# eVV_TopLevel_TMC.net
KiCad netlist of a schematic drawn in Altium Designer
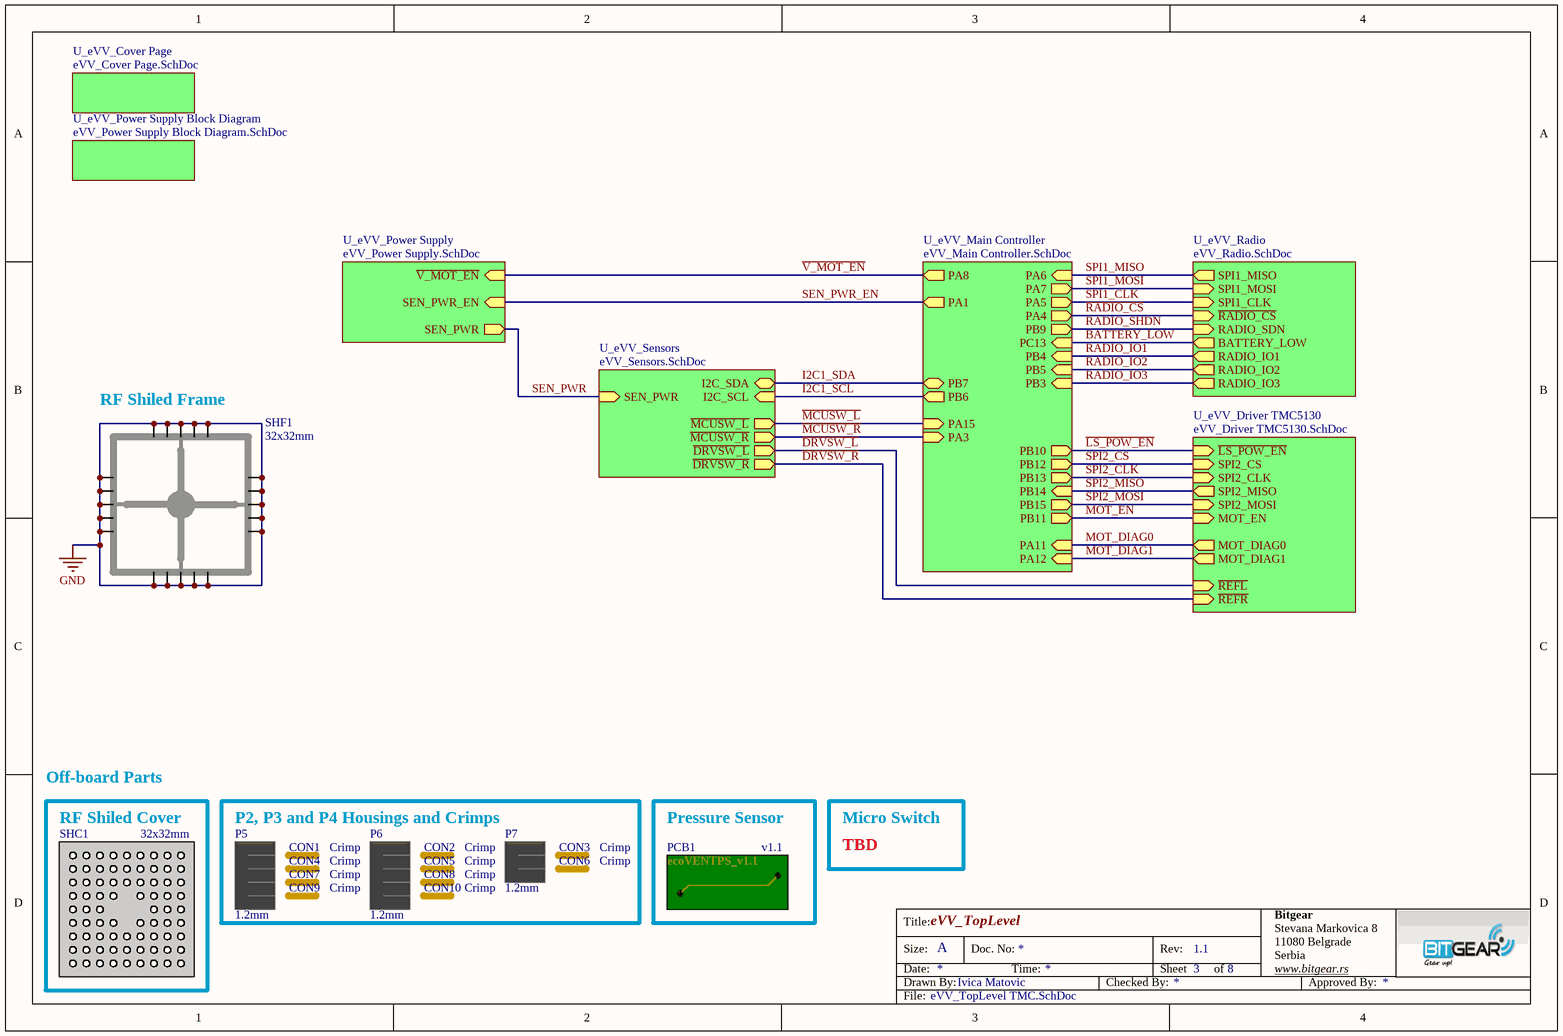
[diagram p0: eVV_TopLevel TMC.SchDoc]

(export (version "E")
  (design (tool "Eeschema 10.0.6"))
  (components
    (comp (ref "CON1")
      (value "Crimp")
      (description "Molex Contact for Pico-EZmate")
      (fields (field (name "MANUFACTURER") "Molex"))
      (libsource (lib "ecoVENTV") (part "0781720410"))
    )
    (comp (ref "CON2")
      (value "Crimp")
      (description "Molex Contact for Pico-EZmate")
      (fields (field (name "MANUFACTURER") "Molex"))
      (libsource (lib "ecoVENTV") (part "0781720410"))
    )
    (comp (ref "CON3")
      (value "Crimp")
      (description "Molex Contact for Pico-EZmate")
      (fields (field (name "MANUFACTURER") "Molex"))
      (libsource (lib "ecoVENTV") (part "0781720410"))
    )
    (comp (ref "CON4")
      (value "Crimp")
      (description "Molex Contact for Pico-EZmate")
      (fields (field (name "MANUFACTURER") "Molex"))
      (libsource (lib "ecoVENTV") (part "0781720410"))
    )
    (comp (ref "CON5")
      (value "Crimp")
      (description "Molex Contact for Pico-EZmate")
      (fields (field (name "MANUFACTURER") "Molex"))
      (libsource (lib "ecoVENTV") (part "0781720410"))
    )
    (comp (ref "CON6")
      (value "Crimp")
      (description "Molex Contact for Pico-EZmate")
      (fields (field (name "MANUFACTURER") "Molex"))
      (libsource (lib "ecoVENTV") (part "0781720410"))
    )
    (comp (ref "CON7")
      (value "Crimp")
      (description "Molex Contact for Pico-EZmate")
      (fields (field (name "MANUFACTURER") "Molex"))
      (libsource (lib "ecoVENTV") (part "0781720410"))
    )
    (comp (ref "CON8")
      (value "Crimp")
      (description "Molex Contact for Pico-EZmate")
      (fields (field (name "MANUFACTURER") "Molex"))
      (libsource (lib "ecoVENTV") (part "0781720410"))
    )
    (comp (ref "CON9")
      (value "Crimp")
      (description "Molex Contact for Pico-EZmate")
      (fields (field (name "MANUFACTURER") "Molex"))
      (libsource (lib "ecoVENTV") (part "0781720410"))
    )
    (comp (ref "CON10")
      (value "Crimp")
      (description "Molex Contact for Pico-EZmate")
      (fields (field (name "MANUFACTURER") "Molex"))
      (libsource (lib "ecoVENTV") (part "0781720410"))
    )
    (comp (ref "P5")
      (value "1.2mm")
      (description "1.2mm pitch Pico-EZmate, Wire to Board, Vertical, with Locks, 1X4")
      (fields (field (name "MANUFACTURER") "Molex"))
      (libsource (lib "ecoVENTV") (part "Receptacle MOLEX Pico-EZmate 1X4 1.2mm"))
    )
    (comp (ref "P6")
      (value "1.2mm")
      (description "1.2mm pitch Pico-EZmate, Wire to Board, Vertical, with Locks, 1X4")
      (fields (field (name "MANUFACTURER") "Molex"))
      (libsource (lib "ecoVENTV") (part "Receptacle MOLEX Pico-EZmate 1X4 1.2mm"))
    )
    (comp (ref "P7")
      (value "1.2mm")
      (description "1.2mm pitch Pico-EZmate, Wire to Board, Vertical, with Locks, 1X2")
      (fields (field (name "MANUFACTURER") "Molex"))
      (libsource (lib "ecoVENTV") (part "Receptacle MOLEX Pico-EZmate 1X2 1.2mm"))
    )
    (comp (ref "PCB1")
      (value "v1.1")
      (description "ecoVENT Pressure Sensor Board")
      (libsource (lib "ecoVENTV") (part "PCB PS v1.1"))
    )
    (comp (ref "SHC1")
      (value "32x32mm")
      (description "Board Level Shield 32X32mm, 6mm Height, Cover")
      (fields (field (name "MANUFACTURER") "Laird Techologies EMI"))
      (libsource (lib "ecoVENTV") (part "BMI-S-204-C"))
    )
    (comp (ref "SHF1")
      (value "32x32mm")
      (footprint "BMI-S-204-F")
      (description "Board Level Shield 32X32mm, 6mm Height, Frame")
      (fields (field (name "MANUFACTURER") "Laird Techologies EMI"))
      (libsource (lib "ecoVENTV") (part "BMI-S-204-F"))
    )
  )
  (nets
    (net (code "27") (name "GND") (class "Default")
      (node (ref "SHF1") (pin "1") (pinfunction "GND_1") (pintype "passive"))
      (node (ref "SHF1") (pin "10") (pinfunction "GND_10") (pintype "passive"))
      (node (ref "SHF1") (pin "11") (pinfunction "GND_11") (pintype "passive"))
      (node (ref "SHF1") (pin "12") (pinfunction "GND_12") (pintype "passive"))
      (node (ref "SHF1") (pin "13") (pinfunction "GND_13") (pintype "passive"))
      (node (ref "SHF1") (pin "14") (pinfunction "GND_14") (pintype "passive"))
      (node (ref "SHF1") (pin "15") (pinfunction "GND_15") (pintype "passive"))
      (node (ref "SHF1") (pin "16") (pinfunction "GND_16") (pintype "passive"))
      (node (ref "SHF1") (pin "17") (pinfunction "GND_17") (pintype "passive"))
      (node (ref "SHF1") (pin "18") (pinfunction "GND_18") (pintype "passive"))
      (node (ref "SHF1") (pin "19") (pinfunction "GND_19") (pintype "passive"))
      (node (ref "SHF1") (pin "2") (pinfunction "GND_2") (pintype "passive"))
      (node (ref "SHF1") (pin "20") (pinfunction "GND_20") (pintype "passive"))
      (node (ref "SHF1") (pin "3") (pinfunction "GND_3") (pintype "passive"))
      (node (ref "SHF1") (pin "4") (pinfunction "GND_4") (pintype "passive"))
      (node (ref "SHF1") (pin "5") (pinfunction "GND_5") (pintype "passive"))
      (node (ref "SHF1") (pin "6") (pinfunction "GND_6") (pintype "passive"))
      (node (ref "SHF1") (pin "7") (pinfunction "GND_7") (pintype "passive"))
      (node (ref "SHF1") (pin "8") (pinfunction "GND_8") (pintype "passive"))
      (node (ref "SHF1") (pin "9") (pinfunction "GND_9") (pintype "passive"))
    )
  )
)
